# breadboard_rev07.net
KiCad netlist of a schematic drawn in EAGLE
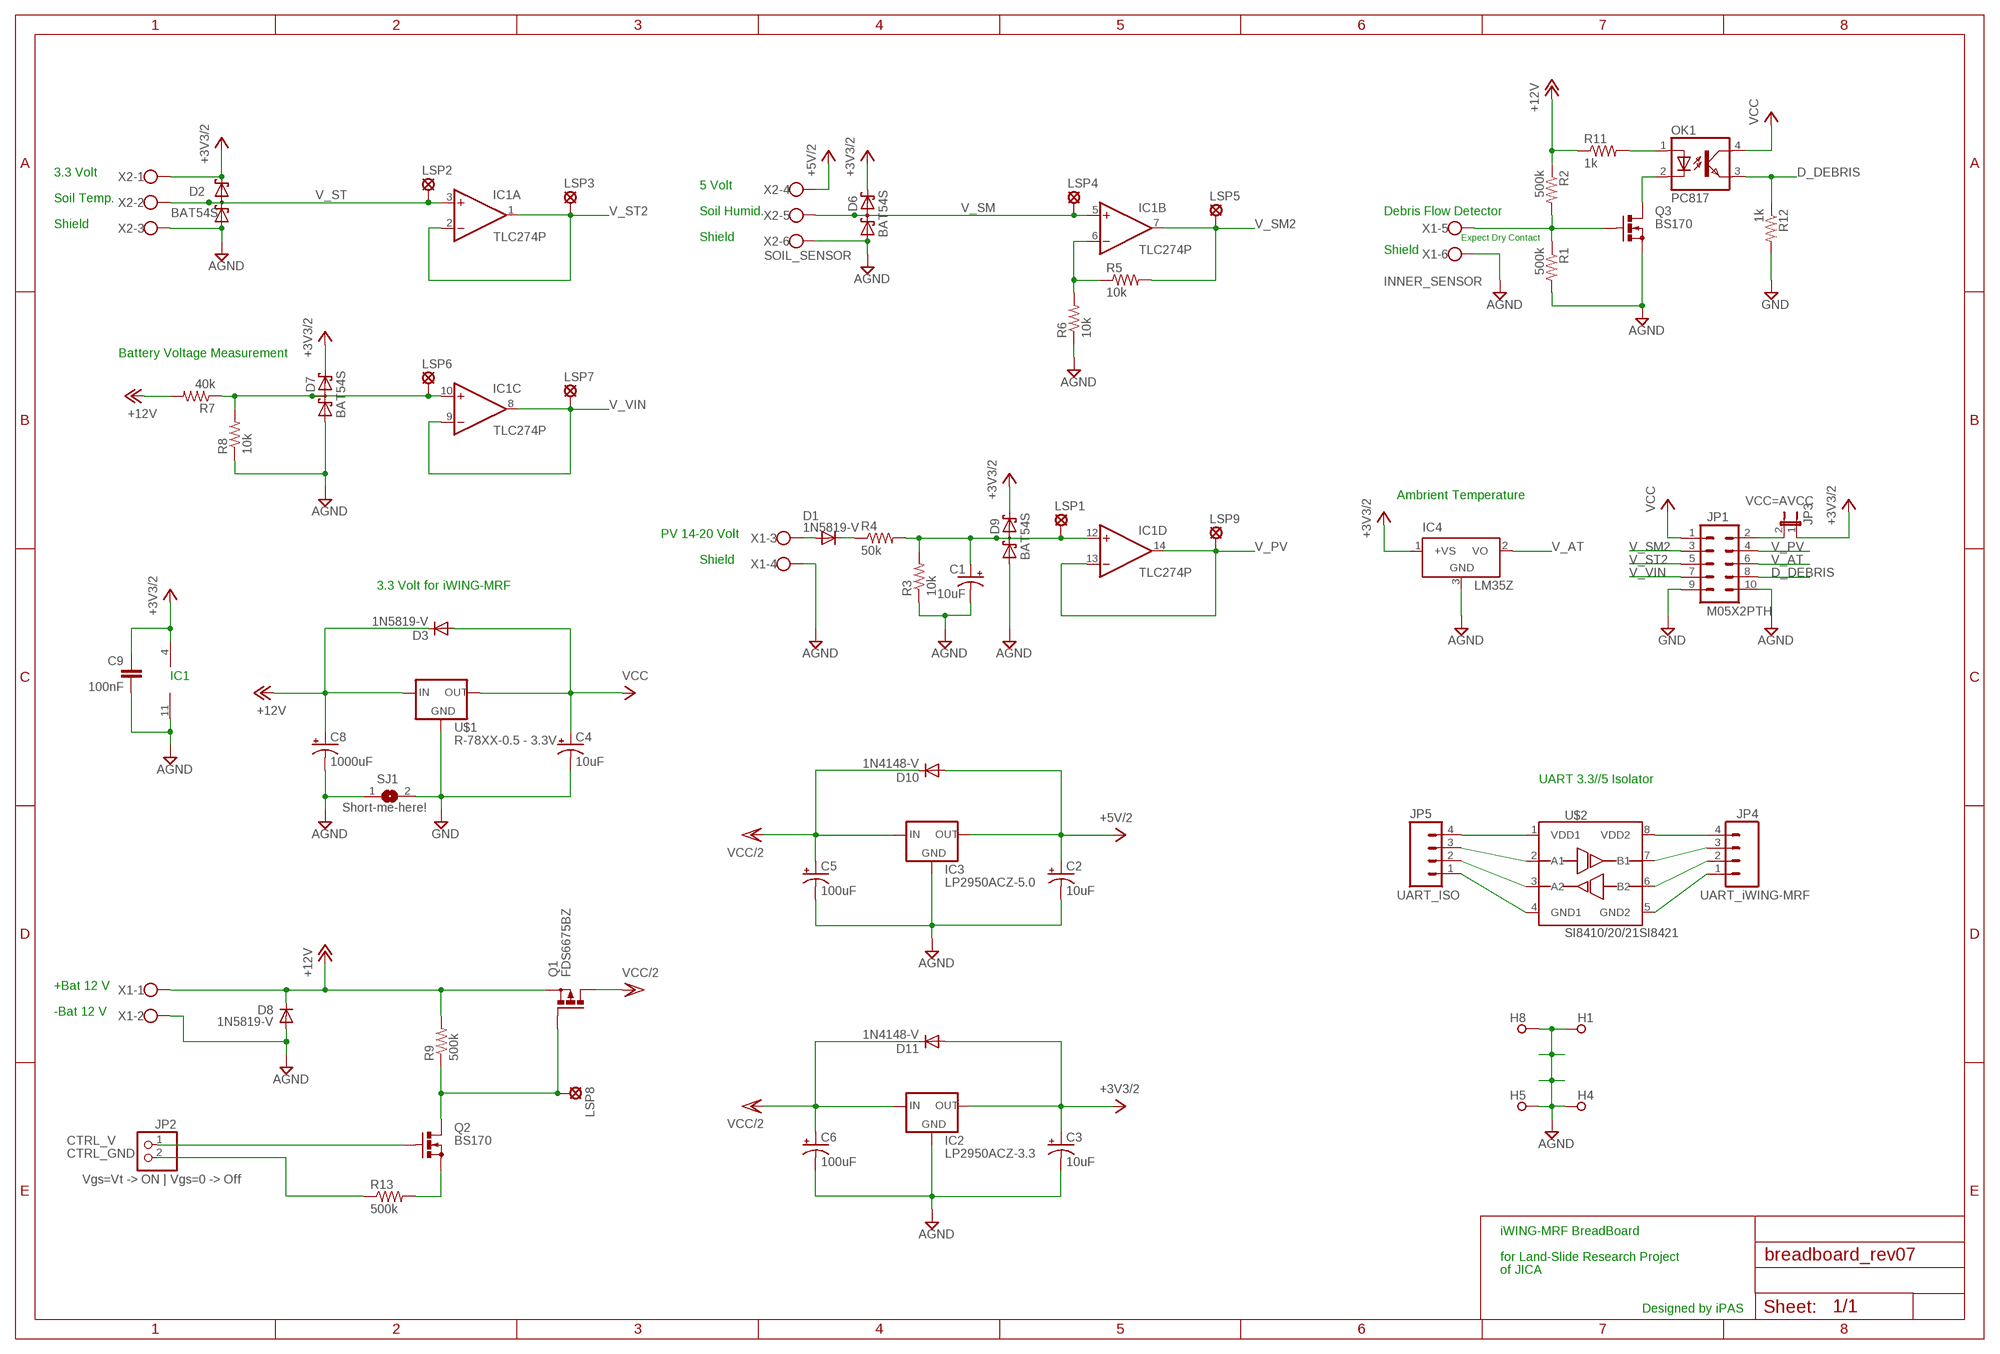
[diagram p0: schematic, sheet 1]

(export (version "E")
  (design (tool "Eeschema 10.0.6"))
  (components
    (comp (ref "C1")
      (value "10uF")
      (footprint "eagle-import:RCL_E2,5-7")
      (libsource (lib "eagle-import") (part "RCL_CPOL-USE2.5-7"))
    )
    (comp (ref "C2")
      (value "10uF")
      (footprint "eagle-import:RCL_E2,5-7")
      (libsource (lib "eagle-import") (part "RCL_CPOL-USE2.5-7"))
    )
    (comp (ref "C3")
      (value "10uF")
      (footprint "eagle-import:RCL_E2,5-7")
      (libsource (lib "eagle-import") (part "RCL_CPOL-USE2.5-7"))
    )
    (comp (ref "C4")
      (value "10uF")
      (footprint "eagle-import:RCL_E2,5-7")
      (libsource (lib "eagle-import") (part "RCL_CPOL-USE2.5-7"))
    )
    (comp (ref "C5")
      (value "100uF")
      (footprint "eagle-import:RCL_E2,5-7")
      (libsource (lib "eagle-import") (part "RCL_CPOL-USE2.5-7"))
    )
    (comp (ref "C6")
      (value "100uF")
      (footprint "eagle-import:RCL_E2,5-7")
      (libsource (lib "eagle-import") (part "RCL_CPOL-USE2.5-7"))
    )
    (comp (ref "C8")
      (value "1000uF")
      (footprint "eagle-import:RCL_E5-13")
      (libsource (lib "eagle-import") (part "RCL_CPOL-USE5-13"))
    )
    (comp (ref "C9")
      (value "100nF")
      (footprint "eagle-import:RCL_C050-025X075")
      (libsource (lib "eagle-import") (part "RCL_C-EU050-025X075"))
    )
    (comp (ref "D1")
      (value "1N5819-V")
      (footprint "eagle-import:DO41-150V")
      (libsource (lib "eagle-import") (part "1N5819-V"))
    )
    (comp (ref "D2")
      (value "BAT54S")
      (footprint "eagle-import:SOT23")
      (libsource (lib "eagle-import") (part "BAT54S"))
    )
    (comp (ref "D3")
      (value "1N5819-V")
      (footprint "eagle-import:DO41-150V")
      (libsource (lib "eagle-import") (part "1N5819-V"))
    )
    (comp (ref "D6")
      (value "BAT54S")
      (footprint "eagle-import:SOT23")
      (libsource (lib "eagle-import") (part "BAT54S"))
    )
    (comp (ref "D7")
      (value "BAT54S")
      (footprint "eagle-import:SOT23")
      (libsource (lib "eagle-import") (part "BAT54S"))
    )
    (comp (ref "D8")
      (value "1N5819-V")
      (footprint "eagle-import:DO41-150V")
      (libsource (lib "eagle-import") (part "1N5819-V"))
    )
    (comp (ref "D9")
      (value "BAT54S")
      (footprint "eagle-import:SOT23")
      (libsource (lib "eagle-import") (part "BAT54S"))
    )
    (comp (ref "D10")
      (value "1N4148-V")
      (footprint "eagle-import:DO35-100V")
      (libsource (lib "eagle-import") (part "1N4148-V"))
    )
    (comp (ref "D11")
      (value "1N4148-V")
      (footprint "eagle-import:DO35-100V")
      (libsource (lib "eagle-import") (part "1N4148-V"))
    )
    (comp (ref "H1")
      (value "SPECIAL_DRILL_0.1560")
      (footprint "eagle-import:PAD_0.1560")
      (libsource (lib "eagle-import") (part "SPECIAL_DRILL_0.1560"))
    )
    (comp (ref "H4")
      (value "SPECIAL_DRILL_0.1560")
      (footprint "eagle-import:PAD_0.1560")
      (libsource (lib "eagle-import") (part "SPECIAL_DRILL_0.1560"))
    )
    (comp (ref "H5")
      (value "SPECIAL_DRILL_0.1560")
      (footprint "eagle-import:PAD_0.1560")
      (libsource (lib "eagle-import") (part "SPECIAL_DRILL_0.1560"))
    )
    (comp (ref "H8")
      (value "SPECIAL_DRILL_0.1560")
      (footprint "eagle-import:PAD_0.1560")
      (libsource (lib "eagle-import") (part "SPECIAL_DRILL_0.1560"))
    )
    (comp (ref "IC1")
      (value "TLC274P")
      (footprint "eagle-import:DIL14")
      (libsource (lib "eagle-import") (part "TLC274P"))
    )
    (comp (ref "IC2")
      (value "LP2950ACZ-3.3")
      (footprint "eagle-import:TO92")
      (libsource (lib "eagle-import") (part "LP2950?ACZ-3.3"))
    )
    (comp (ref "IC3")
      (value "LP2950ACZ-5.0")
      (footprint "eagle-import:TO92")
      (libsource (lib "eagle-import") (part "LP2950?ACZ-5.0"))
    )
    (comp (ref "IC4")
      (value "LM35Z")
      (footprint "eagle-import:TO92")
      (libsource (lib "eagle-import") (part "LM35?Z"))
    )
    (comp (ref "JP1")
      (value "M05X2PTH")
      (footprint "eagle-import:AVR_ICSP")
      (libsource (lib "eagle-import") (part "M05X2PTH"))
    )
    (comp (ref "JP2")
      (value "Vgs=Vt -> ON | Vgs=0 -> Off")
      (footprint "eagle-import:1X02")
      (libsource (lib "eagle-import") (part "PINHD-1X2"))
    )
    (comp (ref "JP3")
      (value "VCC=AVCC")
      (footprint "eagle-import:JUMPER_JP1")
      (libsource (lib "eagle-import") (part "JP1E"))
    )
    (comp (ref "JP4")
      (value "UART_iWING-MRF")
      (footprint "eagle-import:MOLEX-1X4")
      (libsource (lib "eagle-import") (part "M04POLAR"))
    )
    (comp (ref "JP5")
      (value "UART_ISO")
      (footprint "eagle-import:MOLEX-1X4")
      (libsource (lib "eagle-import") (part "M04POLAR"))
    )
    (comp (ref "LSP1")
      (value "LSP13")
      (footprint "eagle-import:LSP13")
      (libsource (lib "eagle-import") (part "LSP13"))
    )
    (comp (ref "LSP2")
      (value "LSP13")
      (footprint "eagle-import:LSP13")
      (libsource (lib "eagle-import") (part "LSP13"))
    )
    (comp (ref "LSP3")
      (value "LSP13")
      (footprint "eagle-import:LSP13")
      (libsource (lib "eagle-import") (part "LSP13"))
    )
    (comp (ref "LSP4")
      (value "LSP13")
      (footprint "eagle-import:LSP13")
      (libsource (lib "eagle-import") (part "LSP13"))
    )
    (comp (ref "LSP5")
      (value "LSP13")
      (footprint "eagle-import:LSP13")
      (libsource (lib "eagle-import") (part "LSP13"))
    )
    (comp (ref "LSP6")
      (value "LSP13")
      (footprint "eagle-import:LSP13")
      (libsource (lib "eagle-import") (part "LSP13"))
    )
    (comp (ref "LSP7")
      (value "LSP13")
      (footprint "eagle-import:LSP13")
      (libsource (lib "eagle-import") (part "LSP13"))
    )
    (comp (ref "LSP8")
      (value "LSP13")
      (footprint "eagle-import:LSP13")
      (libsource (lib "eagle-import") (part "LSP13"))
    )
    (comp (ref "LSP9")
      (value "LSP13")
      (footprint "eagle-import:LSP13")
      (libsource (lib "eagle-import") (part "LSP13"))
    )
    (comp (ref "OK1")
      (value "PC817")
      (footprint "eagle-import:DIL04")
      (fields (field (name "MPN") "PC817X4J000F"))
      (libsource (lib "eagle-import") (part "PC817"))
    )
    (comp (ref "Q1")
      (value "FDS6675BZ")
      (footprint "eagle-import:SO-08")
      (libsource (lib "eagle-import") (part "P-MOSFET-SO8"))
    )
    (comp (ref "Q2")
      (value "BS170")
      (footprint "eagle-import:SOT54E")
      (libsource (lib "eagle-import") (part "BS170"))
    )
    (comp (ref "Q3")
      (value "BS170")
      (footprint "eagle-import:SOT54E")
      (libsource (lib "eagle-import") (part "BS170"))
    )
    (comp (ref "R1")
      (value "500k")
      (footprint "eagle-import:RCL_0204_7")
      (libsource (lib "eagle-import") (part "RCL_R-US_0204/7"))
    )
    (comp (ref "R2")
      (value "500k")
      (footprint "eagle-import:RCL_0204_7")
      (libsource (lib "eagle-import") (part "RCL_R-US_0204/7"))
    )
    (comp (ref "R3")
      (value "10k")
      (footprint "eagle-import:RCL_0204_7")
      (libsource (lib "eagle-import") (part "RCL_R-US_0204/7"))
    )
    (comp (ref "R4")
      (value "50k")
      (footprint "eagle-import:RCL_0204_7")
      (libsource (lib "eagle-import") (part "RCL_R-US_0204/7"))
    )
    (comp (ref "R5")
      (value "10k")
      (footprint "eagle-import:RCL_0204_7")
      (libsource (lib "eagle-import") (part "RCL_R-US_0204/7"))
    )
    (comp (ref "R6")
      (value "10k")
      (footprint "eagle-import:RCL_0204_7")
      (libsource (lib "eagle-import") (part "RCL_R-US_0204/7"))
    )
    (comp (ref "R7")
      (value "40k")
      (footprint "eagle-import:RCL_0204_7")
      (libsource (lib "eagle-import") (part "RCL_R-US_0204/7"))
    )
    (comp (ref "R8")
      (value "10k")
      (footprint "eagle-import:RCL_0204_7")
      (libsource (lib "eagle-import") (part "RCL_R-US_0204/7"))
    )
    (comp (ref "R9")
      (value "500k")
      (footprint "eagle-import:RCL_0204_7")
      (libsource (lib "eagle-import") (part "RCL_R-US_0204/7"))
    )
    (comp (ref "R11")
      (value "1k")
      (footprint "eagle-import:RCL_0204_7")
      (libsource (lib "eagle-import") (part "RCL_R-US_0204/7"))
    )
    (comp (ref "R12")
      (value "1k")
      (footprint "eagle-import:RCL_0204_7")
      (libsource (lib "eagle-import") (part "RCL_R-US_0204/7"))
    )
    (comp (ref "R13")
      (value "500k")
      (footprint "eagle-import:RCL_0204_7")
      (libsource (lib "eagle-import") (part "RCL_R-US_0204/7"))
    )
    (comp (ref "SJ1")
      (value "Short-me-here!")
      (footprint "eagle-import:SJ")
      (libsource (lib "eagle-import") (part "SJ"))
    )
    (comp (ref "U$1")
      (value "R-78XX-0.5 - 3.3V")
      (footprint "eagle-import:SIP3")
      (libsource (lib "eagle-import") (part "R-78XX-0.5"))
    )
    (comp (ref "U$2")
      (value "SI8410/20/21SI8421")
      (footprint "eagle-import:SO-08")
      (libsource (lib "eagle-import") (part "SI8410/20/21SI8421"))
    )
    (comp (ref "X1")
      (value "INNER_SENSOR")
      (footprint "eagle-import:5EHDRC-6P")
      (libsource (lib "eagle-import") (part "5EHDRC-6P"))
    )
    (comp (ref "X2")
      (value "SOIL_SENSOR")
      (footprint "eagle-import:5EHDRC-6P")
      (libsource (lib "eagle-import") (part "5EHDRC-6P"))
    )
  )
  (nets
    (net (code "1") (name "+3V3{slash}2") (class "Default")
      (node (ref "C3") (pin "+") (pinfunction "+_+") (pintype "passive"))
      (node (ref "C9") (pin "1") (pinfunction "1_1") (pintype "passive"))
      (node (ref "D11") (pin "A") (pinfunction "A_A") (pintype "passive"))
      (node (ref "D2") (pin "2") (pinfunction "C2_2") (pintype "passive"))
      (node (ref "D6") (pin "2") (pinfunction "C2_2") (pintype "passive"))
      (node (ref "D7") (pin "2") (pinfunction "C2_2") (pintype "passive"))
      (node (ref "D9") (pin "2") (pinfunction "C2_2") (pintype "passive"))
      (node (ref "IC1") (pin "4") (pinfunction "V+_4") (pintype "power_in"))
      (node (ref "IC2") (pin "1") (pinfunction "OUT_1") (pintype "passive"))
      (node (ref "IC4") (pin "1") (pinfunction "+VS_1") (pintype "input"))
      (node (ref "JP3") (pin "1") (pinfunction "1_1") (pintype "passive"))
      (node (ref "X2") (pin "1") (pinfunction "KL_1") (pintype "passive"))
    )
    (net (code "2") (name "+5V{slash}2") (class "Default")
      (node (ref "C2") (pin "+") (pinfunction "+_+") (pintype "passive"))
      (node (ref "D10") (pin "A") (pinfunction "A_A") (pintype "passive"))
      (node (ref "IC3") (pin "1") (pinfunction "OUT_1") (pintype "passive"))
      (node (ref "X2") (pin "4") (pinfunction "KL_4") (pintype "passive"))
    )
    (net (code "3") (name "+12V") (class "Default")
      (node (ref "C8") (pin "+") (pinfunction "+_+") (pintype "passive"))
      (node (ref "D3") (pin "C") (pinfunction "C_C") (pintype "passive"))
      (node (ref "D8") (pin "C") (pinfunction "C_C") (pintype "passive"))
      (node (ref "Q1") (pin "1") (pinfunction "S_1") (pintype "passive"))
      (node (ref "Q1") (pin "2") (pinfunction "S_2") (pintype "passive"))
      (node (ref "Q1") (pin "3") (pinfunction "S_3") (pintype "passive"))
      (node (ref "R11") (pin "1") (pinfunction "1_1") (pintype "passive"))
      (node (ref "R2") (pin "1") (pinfunction "1_1") (pintype "passive"))
      (node (ref "R7") (pin "2") (pinfunction "2_2") (pintype "passive"))
      (node (ref "R9") (pin "2") (pinfunction "2_2") (pintype "passive"))
      (node (ref "U$1") (pin "1") (pinfunction "IN_1") (pintype "input"))
      (node (ref "X1") (pin "1") (pinfunction "KL_1") (pintype "passive"))
    )
    (net (code "4") (name "/CTRL_GND") (class "Default")
      (node (ref "JP2") (pin "2") (pinfunction "2_2") (pintype "passive"))
      (node (ref "R13") (pin "1") (pinfunction "1_1") (pintype "passive"))
    )
    (net (code "5") (name "/CTRL_V") (class "Default")
      (node (ref "JP2") (pin "1") (pinfunction "1_1") (pintype "passive"))
      (node (ref "Q2") (pin "G") (pinfunction "G_G") (pintype "passive"))
    )
    (net (code "6") (name "/D_DEBRIS") (class "Default")
      (node (ref "JP1") (pin "8") (pinfunction "8_8") (pintype "passive"))
      (node (ref "OK1") (pin "3") (pinfunction "EMIT_3") (pintype "passive"))
      (node (ref "R12") (pin "1") (pinfunction "1_1") (pintype "passive"))
    )
    (net (code "7") (name "/V_AT") (class "Default")
      (node (ref "IC4") (pin "2") (pinfunction "VO_2") (pintype "output"))
      (node (ref "JP1") (pin "6") (pinfunction "6_6") (pintype "passive"))
    )
    (net (code "8") (name "/V_PV") (class "Default")
      (node (ref "IC1") (pin "13") (pinfunction "-IN_13") (pintype "input"))
      (node (ref "IC1") (pin "14") (pinfunction "OUT_14") (pintype "output"))
      (node (ref "JP1") (pin "4") (pinfunction "4_4") (pintype "passive"))
      (node (ref "LSP9") (pin "MP") (pinfunction "MP_MP") (pintype "passive"))
    )
    (net (code "9") (name "/V_SM") (class "Default")
      (node (ref "D6") (pin "3") (pinfunction "C1A2_3") (pintype "passive"))
      (node (ref "IC1") (pin "5") (pinfunction "+IN_5") (pintype "input"))
      (node (ref "LSP4") (pin "MP") (pinfunction "MP_MP") (pintype "passive"))
      (node (ref "X2") (pin "5") (pinfunction "KL_5") (pintype "passive"))
    )
    (net (code "10") (name "/V_SM2") (class "Default")
      (node (ref "IC1") (pin "7") (pinfunction "OUT_7") (pintype "output"))
      (node (ref "JP1") (pin "3") (pinfunction "3_3") (pintype "passive"))
      (node (ref "LSP5") (pin "MP") (pinfunction "MP_MP") (pintype "passive"))
      (node (ref "R5") (pin "2") (pinfunction "2_2") (pintype "passive"))
    )
    (net (code "11") (name "/V_ST") (class "Default")
      (node (ref "D2") (pin "3") (pinfunction "C1A2_3") (pintype "passive"))
      (node (ref "IC1") (pin "3") (pinfunction "+IN_3") (pintype "input"))
      (node (ref "LSP2") (pin "MP") (pinfunction "MP_MP") (pintype "passive"))
      (node (ref "X2") (pin "2") (pinfunction "KL_2") (pintype "passive"))
    )
    (net (code "12") (name "/V_ST2") (class "Default")
      (node (ref "IC1") (pin "1") (pinfunction "OUT_1") (pintype "output"))
      (node (ref "IC1") (pin "2") (pinfunction "-IN_2") (pintype "input"))
      (node (ref "JP1") (pin "5") (pinfunction "5_5") (pintype "passive"))
      (node (ref "LSP3") (pin "MP") (pinfunction "MP_MP") (pintype "passive"))
    )
    (net (code "13") (name "/V_VIN") (class "Default")
      (node (ref "IC1") (pin "8") (pinfunction "OUT_8") (pintype "output"))
      (node (ref "IC1") (pin "9") (pinfunction "-IN_9") (pintype "input"))
      (node (ref "JP1") (pin "7") (pinfunction "7_7") (pintype "passive"))
      (node (ref "LSP7") (pin "MP") (pinfunction "MP_MP") (pintype "passive"))
    )
    (net (code "14") (name "AGND") (class "Default")
      (node (ref "C1") (pin "-") (pinfunction "-_-") (pintype "passive"))
      (node (ref "C2") (pin "-") (pinfunction "-_-") (pintype "passive"))
      (node (ref "C3") (pin "-") (pinfunction "-_-") (pintype "passive"))
      (node (ref "C5") (pin "-") (pinfunction "-_-") (pintype "passive"))
      (node (ref "C6") (pin "-") (pinfunction "-_-") (pintype "passive"))
      (node (ref "C8") (pin "-") (pinfunction "-_-") (pintype "passive"))
      (node (ref "C9") (pin "2") (pinfunction "2_2") (pintype "passive"))
      (node (ref "D2") (pin "1") (pinfunction "A1_1") (pintype "passive"))
      (node (ref "D6") (pin "1") (pinfunction "A1_1") (pintype "passive"))
      (node (ref "D7") (pin "1") (pinfunction "A1_1") (pintype "passive"))
      (node (ref "D8") (pin "A") (pinfunction "A_A") (pintype "passive"))
      (node (ref "D9") (pin "1") (pinfunction "A1_1") (pintype "passive"))
      (node (ref "H1") (pin "1") (pinfunction "1_1") (pintype "passive"))
      (node (ref "H4") (pin "1") (pinfunction "1_1") (pintype "passive"))
      (node (ref "H5") (pin "1") (pinfunction "1_1") (pintype "passive"))
      (node (ref "H8") (pin "1") (pinfunction "1_1") (pintype "passive"))
      (node (ref "IC1") (pin "11") (pinfunction "V-_11") (pintype "power_in"))
      (node (ref "IC2") (pin "2") (pinfunction "GND_2") (pintype "input"))
      (node (ref "IC3") (pin "2") (pinfunction "GND_2") (pintype "input"))
      (node (ref "IC4") (pin "3") (pinfunction "GND_3") (pintype "power_in"))
      (node (ref "JP1") (pin "10") (pinfunction "10_10") (pintype "passive"))
      (node (ref "Q3") (pin "S") (pinfunction "S_S") (pintype "passive"))
      (node (ref "R1") (pin "2") (pinfunction "2_2") (pintype "passive"))
      (node (ref "R3") (pin "1") (pinfunction "1_1") (pintype "passive"))
      (node (ref "R6") (pin "1") (pinfunction "1_1") (pintype "passive"))
      (node (ref "R8") (pin "1") (pinfunction "1_1") (pintype "passive"))
      (node (ref "SJ1") (pin "1") (pinfunction "1_1") (pintype "passive"))
      (node (ref "X1") (pin "2") (pinfunction "KL_2") (pintype "passive"))
      (node (ref "X1") (pin "4") (pinfunction "KL_4") (pintype "passive"))
      (node (ref "X1") (pin "6") (pinfunction "KL_6") (pintype "passive"))
      (node (ref "X2") (pin "3") (pinfunction "KL_3") (pintype "passive"))
      (node (ref "X2") (pin "6") (pinfunction "KL_6") (pintype "passive"))
    )
    (net (code "15") (name "GND") (class "Default")
      (node (ref "C4") (pin "-") (pinfunction "-_-") (pintype "passive"))
      (node (ref "JP1") (pin "9") (pinfunction "9_9") (pintype "passive"))
      (node (ref "R12") (pin "2") (pinfunction "2_2") (pintype "passive"))
      (node (ref "SJ1") (pin "2") (pinfunction "2_2") (pintype "passive"))
      (node (ref "U$1") (pin "2") (pinfunction "GND_2") (pintype "input"))
    )
    (net (code "16") (name "Net-(D1-PadC)") (class "Default")
      (node (ref "D1") (pin "C") (pinfunction "C_C") (pintype "passive"))
      (node (ref "R4") (pin "1") (pinfunction "1_1") (pintype "passive"))
    )
    (net (code "17") (name "Net-(D7-C1A2)") (class "Default")
      (node (ref "D7") (pin "3") (pinfunction "C1A2_3") (pintype "passive"))
      (node (ref "IC1") (pin "10") (pinfunction "+IN_10") (pintype "input"))
      (node (ref "LSP6") (pin "MP") (pinfunction "MP_MP") (pintype "passive"))
      (node (ref "R7") (pin "1") (pinfunction "1_1") (pintype "passive"))
      (node (ref "R8") (pin "2") (pinfunction "2_2") (pintype "passive"))
    )
    (net (code "18") (name "Net-(D9-C1A2)") (class "Default")
      (node (ref "C1") (pin "+") (pinfunction "+_+") (pintype "passive"))
      (node (ref "D9") (pin "3") (pinfunction "C1A2_3") (pintype "passive"))
      (node (ref "IC1") (pin "12") (pinfunction "+IN_12") (pintype "input"))
      (node (ref "LSP1") (pin "MP") (pinfunction "MP_MP") (pintype "passive"))
      (node (ref "R3") (pin "2") (pinfunction "2_2") (pintype "passive"))
      (node (ref "R4") (pin "2") (pinfunction "2_2") (pintype "passive"))
    )
    (net (code "19") (name "Net-(IC1B--IN)") (class "Default")
      (node (ref "IC1") (pin "6") (pinfunction "-IN_6") (pintype "input"))
      (node (ref "R5") (pin "1") (pinfunction "1_1") (pintype "passive"))
      (node (ref "R6") (pin "2") (pinfunction "2_2") (pintype "passive"))
    )
    (net (code "20") (name "Net-(JP1-Pad2)") (class "Default")
      (node (ref "JP1") (pin "2") (pinfunction "2_2") (pintype "passive"))
      (node (ref "JP3") (pin "2") (pinfunction "2_2") (pintype "passive"))
    )
    (net (code "21") (name "Net-(OK1-A)") (class "Default")
      (node (ref "OK1") (pin "1") (pinfunction "A_1") (pintype "passive"))
      (node (ref "R11") (pin "2") (pinfunction "2_2") (pintype "passive"))
    )
    (net (code "22") (name "Net-(OK1-C)") (class "Default")
      (node (ref "OK1") (pin "2") (pinfunction "C_2") (pintype "passive"))
      (node (ref "Q3") (pin "D") (pinfunction "D_D") (pintype "passive"))
    )
    (net (code "23") (name "Net-(Q1-G)") (class "Default")
      (node (ref "LSP8") (pin "MP") (pinfunction "MP_MP") (pintype "passive"))
      (node (ref "Q1") (pin "4") (pinfunction "G_4") (pintype "passive"))
      (node (ref "Q2") (pin "D") (pinfunction "D_D") (pintype "passive"))
      (node (ref "R9") (pin "1") (pinfunction "1_1") (pintype "passive"))
    )
    (net (code "24") (name "Net-(Q2-PadS)") (class "Default")
      (node (ref "Q2") (pin "S") (pinfunction "S_S") (pintype "passive"))
      (node (ref "R13") (pin "2") (pinfunction "2_2") (pintype "passive"))
    )
    (net (code "25") (name "Net-(U$2-A1)") (class "Default")
      (node (ref "JP5") (pin "3") (pinfunction "3_3") (pintype "passive"))
      (node (ref "U$2") (pin "2") (pinfunction "A1_2") (pintype "input"))
    )
    (net (code "26") (name "Net-(U$2-A2)") (class "Default")
      (node (ref "JP5") (pin "2") (pinfunction "2_2") (pintype "passive"))
      (node (ref "U$2") (pin "3") (pinfunction "A2_3") (pintype "output"))
    )
    (net (code "27") (name "Net-(U$2-B1)") (class "Default")
      (node (ref "JP4") (pin "3") (pinfunction "3_3") (pintype "passive"))
      (node (ref "U$2") (pin "7") (pinfunction "B1_7") (pintype "output"))
    )
    (net (code "28") (name "Net-(U$2-B2)") (class "Default")
      (node (ref "JP4") (pin "2") (pinfunction "2_2") (pintype "passive"))
      (node (ref "U$2") (pin "6") (pinfunction "B2_6") (pintype "input"))
    )
    (net (code "29") (name "Net-(U$2-GND1)") (class "Default")
      (node (ref "JP5") (pin "1") (pinfunction "1_1") (pintype "passive"))
      (node (ref "U$2") (pin "4") (pinfunction "GND1_4") (pintype "power_in"))
    )
    (net (code "30") (name "Net-(U$2-GND2)") (class "Default")
      (node (ref "JP4") (pin "1") (pinfunction "1_1") (pintype "passive"))
      (node (ref "U$2") (pin "5") (pinfunction "GND2_5") (pintype "power_in"))
    )
    (net (code "31") (name "Net-(U$2-VDD1)") (class "Default")
      (node (ref "JP5") (pin "4") (pinfunction "4_4") (pintype "passive"))
      (node (ref "U$2") (pin "1") (pinfunction "VDD1_1") (pintype "power_in"))
    )
    (net (code "32") (name "Net-(U$2-VDD2)") (class "Default")
      (node (ref "JP4") (pin "4") (pinfunction "4_4") (pintype "passive"))
      (node (ref "U$2") (pin "8") (pinfunction "VDD2_8") (pintype "power_in"))
    )
    (net (code "33") (name "Net-(X1C-KL)") (class "Default")
      (node (ref "D1") (pin "A") (pinfunction "A_A") (pintype "passive"))
      (node (ref "X1") (pin "3") (pinfunction "KL_3") (pintype "passive"))
    )
    (net (code "34") (name "Net-(X1E-KL)") (class "Default")
      (node (ref "Q3") (pin "G") (pinfunction "G_G") (pintype "passive"))
      (node (ref "R1") (pin "1") (pinfunction "1_1") (pintype "passive"))
      (node (ref "R2") (pin "2") (pinfunction "2_2") (pintype "passive"))
      (node (ref "X1") (pin "5") (pinfunction "KL_5") (pintype "passive"))
    )
    (net (code "35") (name "VCC") (class "Default")
      (node (ref "C4") (pin "+") (pinfunction "+_+") (pintype "passive"))
      (node (ref "D3") (pin "A") (pinfunction "A_A") (pintype "passive"))
      (node (ref "JP1") (pin "1") (pinfunction "1_1") (pintype "passive"))
      (node (ref "OK1") (pin "4") (pinfunction "COL_4") (pintype "passive"))
      (node (ref "U$1") (pin "3") (pinfunction "OUT_3") (pintype "passive"))
    )
    (net (code "36") (name "VCC{slash}2") (class "Default")
      (node (ref "C5") (pin "+") (pinfunction "+_+") (pintype "passive"))
      (node (ref "C6") (pin "+") (pinfunction "+_+") (pintype "passive"))
      (node (ref "D10") (pin "C") (pinfunction "C_C") (pintype "passive"))
      (node (ref "D11") (pin "C") (pinfunction "C_C") (pintype "passive"))
      (node (ref "IC2") (pin "3") (pinfunction "IN_3") (pintype "input"))
      (node (ref "IC3") (pin "3") (pinfunction "IN_3") (pintype "input"))
      (node (ref "Q1") (pin "5") (pinfunction "D_5") (pintype "passive"))
      (node (ref "Q1") (pin "6") (pinfunction "D_6") (pintype "passive"))
      (node (ref "Q1") (pin "7") (pinfunction "D_7") (pintype "passive"))
      (node (ref "Q1") (pin "8") (pinfunction "D_8") (pintype "passive"))
    )
  )
)
